# task8.net
KiCad netlist of a schematic drawn in EAGLE
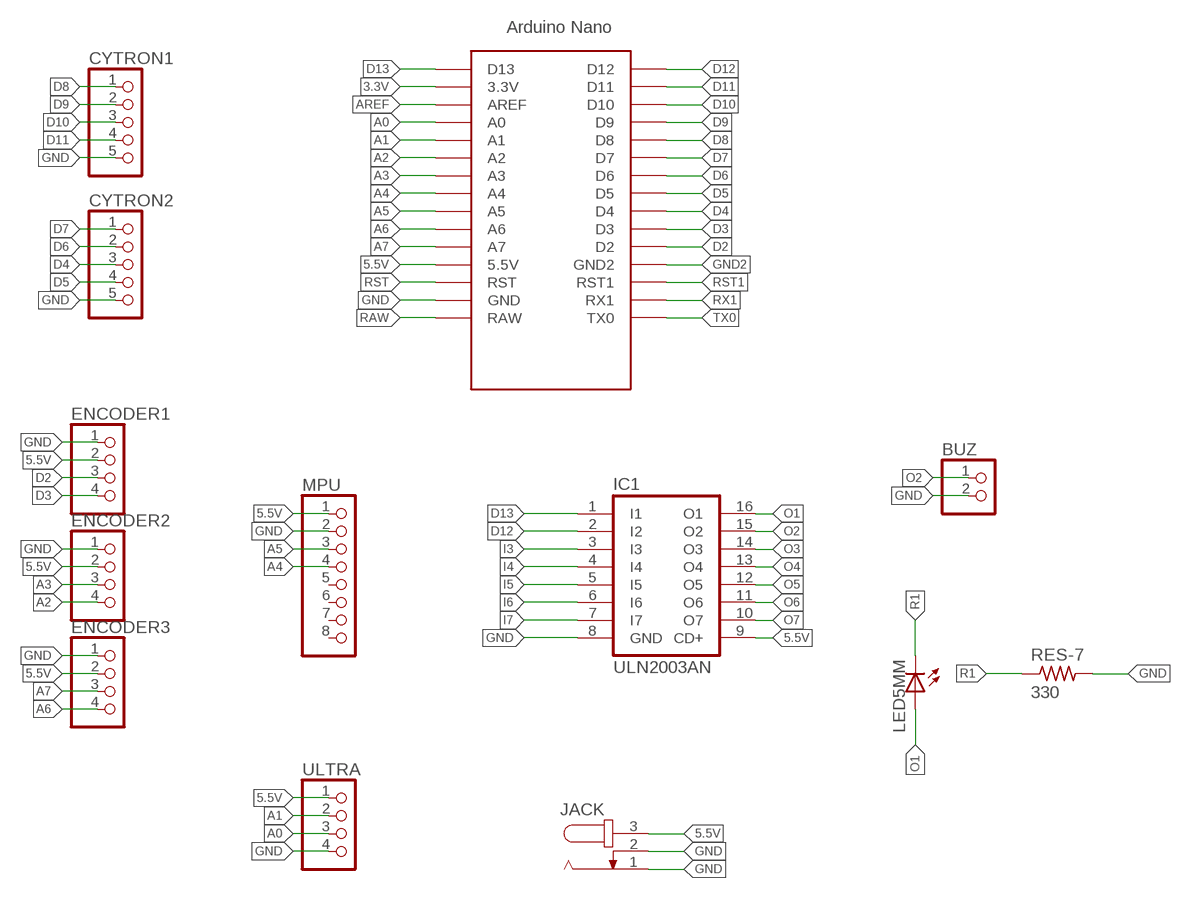
[diagram p0: schematic, sheet 1]

(export (version "E")
  (design (tool "Eeschema 10.0.6"))
  (components
    (comp (ref "330")
      (value "RES-7")
      (footprint "eagle-import:0204_7")
      (libsource (lib "eagle-import") (part "RES-7"))
    )
    (comp (ref "BUZ")
      (value "PINHD-1X2")
      (footprint "eagle-import:1X02")
      (libsource (lib "eagle-import") (part "PINHD-1X2"))
    )
    (comp (ref "CYTRON1")
      (value "PINHD-1X5")
      (footprint "eagle-import:1X05")
      (libsource (lib "eagle-import") (part "PINHD-1X5"))
    )
    (comp (ref "CYTRON2")
      (value "PINHD-1X5")
      (footprint "eagle-import:1X05")
      (libsource (lib "eagle-import") (part "PINHD-1X5"))
    )
    (comp (ref "ENCODER1")
      (value "PINHD-1X4")
      (footprint "eagle-import:1X04")
      (libsource (lib "eagle-import") (part "PINHD-1X4"))
    )
    (comp (ref "ENCODER2")
      (value "PINHD-1X4")
      (footprint "eagle-import:1X04")
      (libsource (lib "eagle-import") (part "PINHD-1X4"))
    )
    (comp (ref "ENCODER3")
      (value "PINHD-1X4")
      (footprint "eagle-import:1X04")
      (libsource (lib "eagle-import") (part "PINHD-1X4"))
    )
    (comp (ref "IC1")
      (value "ULN2003AN")
      (footprint "eagle-import:DIL16")
      (libsource (lib "eagle-import") (part "ULN2003AN"))
    )
    (comp (ref "JACK")
      (value "JACK-PLUG0")
      (footprint "eagle-import:SPC4077")
      (libsource (lib "eagle-import") (part "JACK-PLUG0"))
    )
    (comp (ref "MPU")
      (value "PINHD-1X8")
      (footprint "eagle-import:1X08")
      (libsource (lib "eagle-import") (part "PINHD-1X8"))
    )
    (comp (ref "U$1")
      (value "ARDUINO_NANO")
      (footprint "eagle-import:NANO")
      (libsource (lib "eagle-import") (part "ARDUINO_NANO"))
    )
    (comp (ref "U$3")
      (value "LED5MM")
      (footprint "eagle-import:LED5MM")
      (libsource (lib "eagle-import") (part "LED5MM"))
    )
    (comp (ref "ULTRA")
      (value "PINHD-1X4")
      (footprint "eagle-import:1X04")
      (libsource (lib "eagle-import") (part "PINHD-1X4"))
    )
  )
  (nets
    (net (code "1") (name "3.3V") (class "Default")
      (node (ref "U$1") (pin "3.3V") (pinfunction "3.3V_3.3V") (pintype "bidirectional"))
    )
    (net (code "2") (name "5.5V") (class "Default")
      (node (ref "ENCODER1") (pin "2") (pinfunction "2_2") (pintype "passive"))
      (node (ref "ENCODER2") (pin "2") (pinfunction "2_2") (pintype "passive"))
      (node (ref "ENCODER3") (pin "2") (pinfunction "2_2") (pintype "passive"))
      (node (ref "IC1") (pin "9") (pinfunction "CD+_9") (pintype "passive"))
      (node (ref "JACK") (pin "3") (pinfunction "3_3") (pintype "passive"))
      (node (ref "MPU") (pin "1") (pinfunction "1_1") (pintype "passive"))
      (node (ref "U$1") (pin "5V") (pinfunction "5.5V_5V") (pintype "bidirectional"))
      (node (ref "ULTRA") (pin "1") (pinfunction "1_1") (pintype "passive"))
    )
    (net (code "3") (name "A0") (class "Default")
      (node (ref "U$1") (pin "A0") (pinfunction "A0_A0") (pintype "bidirectional"))
      (node (ref "ULTRA") (pin "3") (pinfunction "3_3") (pintype "passive"))
    )
    (net (code "4") (name "A1") (class "Default")
      (node (ref "U$1") (pin "A1") (pinfunction "A1_A1") (pintype "bidirectional"))
      (node (ref "ULTRA") (pin "2") (pinfunction "2_2") (pintype "passive"))
    )
    (net (code "5") (name "A2") (class "Default")
      (node (ref "ENCODER2") (pin "4") (pinfunction "4_4") (pintype "passive"))
      (node (ref "U$1") (pin "A2") (pinfunction "A2_A2") (pintype "bidirectional"))
    )
    (net (code "6") (name "A3") (class "Default")
      (node (ref "ENCODER2") (pin "3") (pinfunction "3_3") (pintype "passive"))
      (node (ref "U$1") (pin "A3") (pinfunction "A3_A3") (pintype "bidirectional"))
    )
    (net (code "7") (name "A4") (class "Default")
      (node (ref "MPU") (pin "4") (pinfunction "4_4") (pintype "passive"))
      (node (ref "U$1") (pin "A4") (pinfunction "A4_A4") (pintype "bidirectional"))
    )
    (net (code "8") (name "A5") (class "Default")
      (node (ref "MPU") (pin "3") (pinfunction "3_3") (pintype "passive"))
      (node (ref "U$1") (pin "A5") (pinfunction "A5_A5") (pintype "bidirectional"))
    )
    (net (code "9") (name "A6") (class "Default")
      (node (ref "ENCODER3") (pin "4") (pinfunction "4_4") (pintype "passive"))
      (node (ref "U$1") (pin "A6") (pinfunction "A6_A6") (pintype "bidirectional"))
    )
    (net (code "10") (name "A7") (class "Default")
      (node (ref "ENCODER3") (pin "3") (pinfunction "3_3") (pintype "passive"))
      (node (ref "U$1") (pin "A7") (pinfunction "A7_A7") (pintype "bidirectional"))
    )
    (net (code "11") (name "AREF") (class "Default")
      (node (ref "U$1") (pin "AREF") (pinfunction "AREF_AREF") (pintype "bidirectional"))
    )
    (net (code "12") (name "D2") (class "Default")
      (node (ref "ENCODER1") (pin "3") (pinfunction "3_3") (pintype "passive"))
      (node (ref "U$1") (pin "D2") (pinfunction "D2_D2") (pintype "bidirectional"))
    )
    (net (code "13") (name "D3") (class "Default")
      (node (ref "ENCODER1") (pin "4") (pinfunction "4_4") (pintype "passive"))
      (node (ref "U$1") (pin "D3") (pinfunction "D3_D3") (pintype "bidirectional"))
    )
    (net (code "14") (name "D4") (class "Default")
      (node (ref "CYTRON2") (pin "3") (pinfunction "3_3") (pintype "passive"))
      (node (ref "U$1") (pin "D4") (pinfunction "D4_D4") (pintype "bidirectional"))
    )
    (net (code "15") (name "D5") (class "Default")
      (node (ref "CYTRON2") (pin "4") (pinfunction "4_4") (pintype "passive"))
      (node (ref "U$1") (pin "D5") (pinfunction "D5_D5") (pintype "bidirectional"))
    )
    (net (code "16") (name "D6") (class "Default")
      (node (ref "CYTRON2") (pin "2") (pinfunction "2_2") (pintype "passive"))
      (node (ref "U$1") (pin "D6") (pinfunction "D6_D6") (pintype "bidirectional"))
    )
    (net (code "17") (name "D7") (class "Default")
      (node (ref "CYTRON2") (pin "1") (pinfunction "1_1") (pintype "passive"))
      (node (ref "U$1") (pin "D7") (pinfunction "D7_D7") (pintype "bidirectional"))
    )
    (net (code "18") (name "D8") (class "Default")
      (node (ref "CYTRON1") (pin "1") (pinfunction "1_1") (pintype "passive"))
      (node (ref "U$1") (pin "D8") (pinfunction "D8_D8") (pintype "bidirectional"))
    )
    (net (code "19") (name "D9") (class "Default")
      (node (ref "CYTRON1") (pin "2") (pinfunction "2_2") (pintype "passive"))
      (node (ref "U$1") (pin "D9") (pinfunction "D9_D9") (pintype "bidirectional"))
    )
    (net (code "20") (name "D10") (class "Default")
      (node (ref "CYTRON1") (pin "3") (pinfunction "3_3") (pintype "passive"))
      (node (ref "U$1") (pin "D10") (pinfunction "D10_D10") (pintype "bidirectional"))
    )
    (net (code "21") (name "D11") (class "Default")
      (node (ref "CYTRON1") (pin "4") (pinfunction "4_4") (pintype "passive"))
      (node (ref "U$1") (pin "D11") (pinfunction "D11_D11") (pintype "bidirectional"))
    )
    (net (code "22") (name "D12") (class "Default")
      (node (ref "IC1") (pin "2") (pinfunction "I2_2") (pintype "input"))
      (node (ref "U$1") (pin "D12") (pinfunction "D12_D12") (pintype "bidirectional"))
    )
    (net (code "23") (name "D13") (class "Default")
      (node (ref "IC1") (pin "1") (pinfunction "I1_1") (pintype "input"))
      (node (ref "U$1") (pin "D13") (pinfunction "D13_D13") (pintype "bidirectional"))
    )
    (net (code "24") (name "GND") (class "Default")
      (node (ref "330") (pin "2") (pinfunction "2_2") (pintype "passive"))
      (node (ref "BUZ") (pin "2") (pinfunction "2_2") (pintype "passive"))
      (node (ref "CYTRON1") (pin "5") (pinfunction "5_5") (pintype "passive"))
      (node (ref "CYTRON2") (pin "5") (pinfunction "5_5") (pintype "passive"))
      (node (ref "ENCODER1") (pin "1") (pinfunction "1_1") (pintype "passive"))
      (node (ref "ENCODER2") (pin "1") (pinfunction "1_1") (pintype "passive"))
      (node (ref "ENCODER3") (pin "1") (pinfunction "1_1") (pintype "passive"))
      (node (ref "IC1") (pin "8") (pinfunction "GND_8") (pintype "power_in"))
      (node (ref "JACK") (pin "1") (pinfunction "1_1") (pintype "passive"))
      (node (ref "JACK") (pin "2") (pinfunction "2_2") (pintype "passive"))
      (node (ref "MPU") (pin "2") (pinfunction "2_2") (pintype "passive"))
      (node (ref "U$1") (pin "GND") (pinfunction "GND_GND") (pintype "bidirectional"))
      (node (ref "ULTRA") (pin "4") (pinfunction "4_4") (pintype "passive"))
    )
    (net (code "25") (name "GND2") (class "Default")
      (node (ref "U$1") (pin "GND1") (pinfunction "GND2_GND1") (pintype "bidirectional"))
    )
    (net (code "26") (name "I3") (class "Default")
      (node (ref "IC1") (pin "3") (pinfunction "I3_3") (pintype "input"))
    )
    (net (code "27") (name "I4") (class "Default")
      (node (ref "IC1") (pin "4") (pinfunction "I4_4") (pintype "input"))
    )
    (net (code "28") (name "I5") (class "Default")
      (node (ref "IC1") (pin "5") (pinfunction "I5_5") (pintype "input"))
    )
    (net (code "29") (name "I6") (class "Default")
      (node (ref "IC1") (pin "6") (pinfunction "I6_6") (pintype "input"))
    )
    (net (code "30") (name "I7") (class "Default")
      (node (ref "IC1") (pin "7") (pinfunction "I7_7") (pintype "input"))
    )
    (net (code "31") (name "O1") (class "Default")
      (node (ref "IC1") (pin "16") (pinfunction "O1_16") (pintype "open_collector"))
      (node (ref "U$3") (pin "A") (pinfunction "A_A") (pintype "passive"))
    )
    (net (code "32") (name "O2") (class "Default")
      (node (ref "BUZ") (pin "1") (pinfunction "1_1") (pintype "passive"))
      (node (ref "IC1") (pin "15") (pinfunction "O2_15") (pintype "open_collector"))
    )
    (net (code "33") (name "O3") (class "Default")
      (node (ref "IC1") (pin "14") (pinfunction "O3_14") (pintype "open_collector"))
    )
    (net (code "34") (name "O4") (class "Default")
      (node (ref "IC1") (pin "13") (pinfunction "O4_13") (pintype "open_collector"))
    )
    (net (code "35") (name "O5") (class "Default")
      (node (ref "IC1") (pin "12") (pinfunction "O5_12") (pintype "open_collector"))
    )
    (net (code "36") (name "O6") (class "Default")
      (node (ref "IC1") (pin "11") (pinfunction "O6_11") (pintype "open_collector"))
    )
    (net (code "37") (name "O7") (class "Default")
      (node (ref "IC1") (pin "10") (pinfunction "O7_10") (pintype "open_collector"))
    )
    (net (code "38") (name "R1") (class "Default")
      (node (ref "330") (pin "1") (pinfunction "1_1") (pintype "passive"))
      (node (ref "U$3") (pin "K") (pinfunction "C_K") (pintype "passive"))
    )
    (net (code "39") (name "RAW") (class "Default")
      (node (ref "U$1") (pin "RAW") (pinfunction "RAW_RAW") (pintype "bidirectional"))
    )
    (net (code "40") (name "RST") (class "Default")
      (node (ref "U$1") (pin "RST") (pinfunction "RST_RST") (pintype "bidirectional"))
    )
    (net (code "41") (name "RST1") (class "Default")
      (node (ref "U$1") (pin "RST1") (pinfunction "RST1_RST1") (pintype "bidirectional"))
    )
    (net (code "42") (name "RX1") (class "Default")
      (node (ref "U$1") (pin "RX1") (pinfunction "RX1_RX1") (pintype "bidirectional"))
    )
    (net (code "43") (name "TX0") (class "Default")
      (node (ref "U$1") (pin "TX0") (pinfunction "TX0_TX0") (pintype "bidirectional"))
    )
    (net (code "44") (name "unconnected-(MPU-Pad5)") (class "Default")
      (node (ref "MPU") (pin "5") (pinfunction "5_5") (pintype "passive"))
    )
    (net (code "45") (name "unconnected-(MPU-Pad6)") (class "Default")
      (node (ref "MPU") (pin "6") (pinfunction "6_6") (pintype "passive"))
    )
    (net (code "46") (name "unconnected-(MPU-Pad7)") (class "Default")
      (node (ref "MPU") (pin "7") (pinfunction "7_7") (pintype "passive"))
    )
    (net (code "47") (name "unconnected-(MPU-Pad8)") (class "Default")
      (node (ref "MPU") (pin "8") (pinfunction "8_8") (pintype "passive"))
    )
  )
)
